# MrMIDI_L1.net
KiCad netlist of a schematic drawn in EAGLE
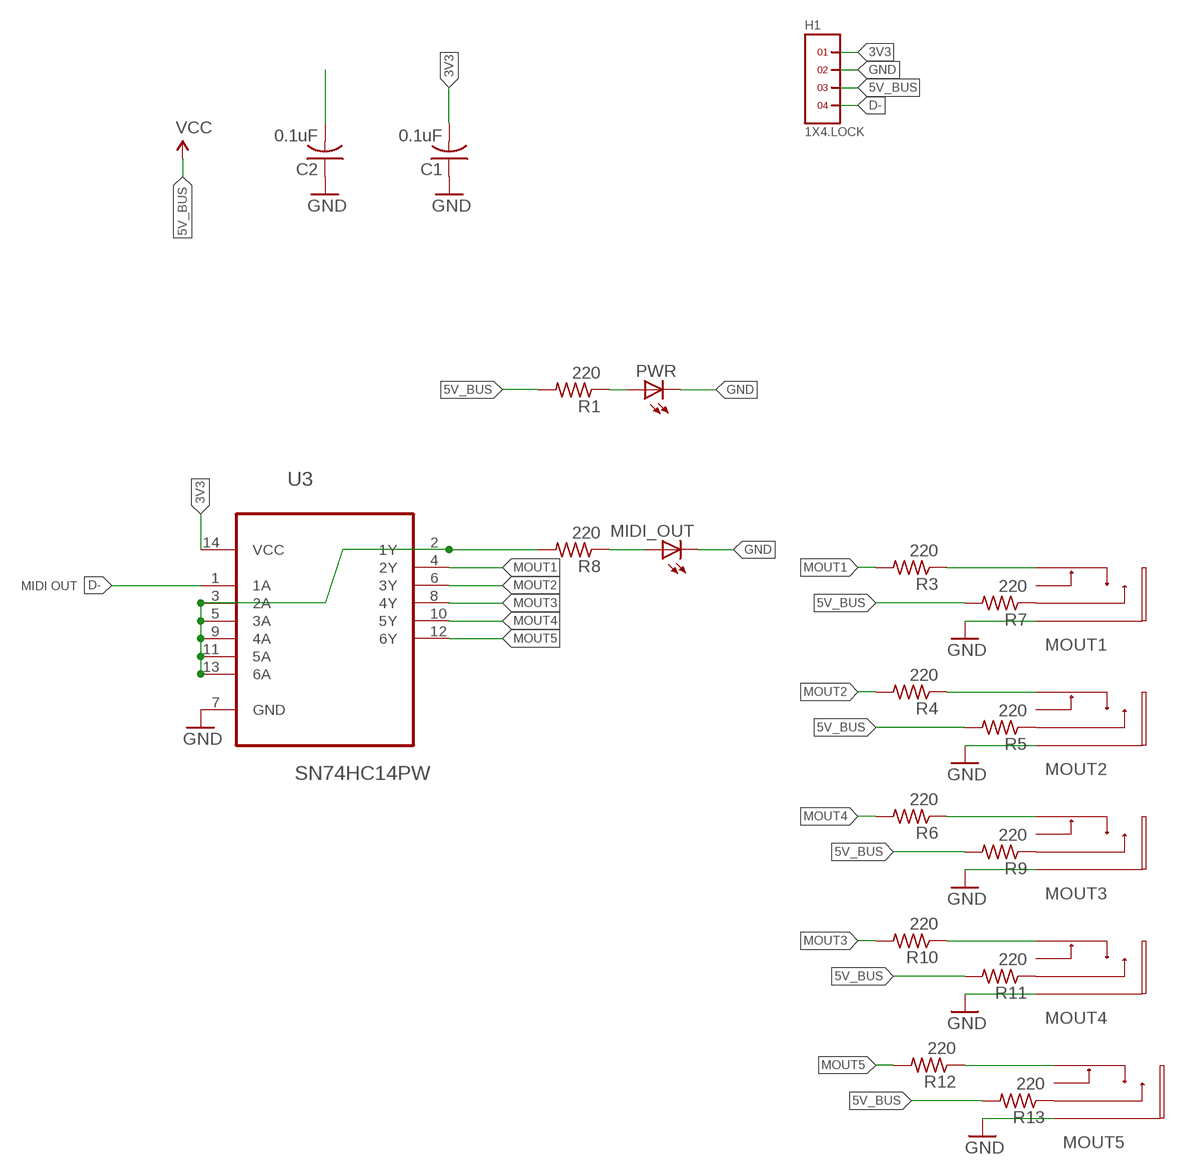
[diagram p0: schematic, sheet 1]

(export (version "E")
  (design (tool "Eeschema 10.0.6"))
  (components
    (comp (ref "C1")
      (value "0.1uF")
      (footprint "eagle-import:RCL_C0603K")
      (libsource (lib "eagle-import") (part "RCL_C-USC0603K"))
    )
    (comp (ref "C2")
      (value "0.1uF")
      (footprint "eagle-import:RCL_C0603K")
      (libsource (lib "eagle-import") (part "RCL_C-USC0603K"))
    )
    (comp (ref "H1")
      (value "1X4.LOCK")
      (footprint "eagle-import:1X4.LOCK")
      (libsource (lib "eagle-import") (part "1X4.LOCK"))
    )
    (comp (ref "MIDI_OUT")
      (value "LEDCHIPLED_0603")
      (footprint "eagle-import:CHIPLED_0603")
      (libsource (lib "eagle-import") (part "LEDCHIPLED_0603"))
    )
    (comp (ref "MOUT1")
      (value "PJ327E")
      (footprint "eagle-import:PJ327")
      (libsource (lib "eagle-import") (part "PJ327E"))
    )
    (comp (ref "MOUT2")
      (value "PJ327E")
      (footprint "eagle-import:PJ327")
      (libsource (lib "eagle-import") (part "PJ327E"))
    )
    (comp (ref "MOUT3")
      (value "PJ327E")
      (footprint "eagle-import:PJ327")
      (libsource (lib "eagle-import") (part "PJ327E"))
    )
    (comp (ref "MOUT4")
      (value "PJ327E")
      (footprint "eagle-import:PJ327")
      (libsource (lib "eagle-import") (part "PJ327E"))
    )
    (comp (ref "MOUT5")
      (value "PJ327E")
      (footprint "eagle-import:PJ327")
      (libsource (lib "eagle-import") (part "PJ327E"))
    )
    (comp (ref "PWR")
      (value "LEDCHIPLED_0603")
      (footprint "eagle-import:CHIPLED_0603")
      (libsource (lib "eagle-import") (part "LEDCHIPLED_0603"))
    )
    (comp (ref "R1")
      (value "220")
      (footprint "eagle-import:RCL_R0402")
      (libsource (lib "eagle-import") (part "RCL_R-US_R0402"))
    )
    (comp (ref "R3")
      (value "220")
      (footprint "eagle-import:RCL_R0402")
      (libsource (lib "eagle-import") (part "RCL_R-US_R0402"))
    )
    (comp (ref "R4")
      (value "220")
      (footprint "eagle-import:RCL_R0402")
      (libsource (lib "eagle-import") (part "RCL_R-US_R0402"))
    )
    (comp (ref "R5")
      (value "220")
      (footprint "eagle-import:RCL_R0402")
      (libsource (lib "eagle-import") (part "RCL_R-US_R0402"))
    )
    (comp (ref "R6")
      (value "220")
      (footprint "eagle-import:RCL_R0402")
      (libsource (lib "eagle-import") (part "RCL_R-US_R0402"))
    )
    (comp (ref "R7")
      (value "220")
      (footprint "eagle-import:RCL_R0402")
      (libsource (lib "eagle-import") (part "RCL_R-US_R0402"))
    )
    (comp (ref "R8")
      (value "220")
      (footprint "eagle-import:RCL_R0402")
      (libsource (lib "eagle-import") (part "RCL_R-US_R0402"))
    )
    (comp (ref "R9")
      (value "220")
      (footprint "eagle-import:RCL_R0402")
      (libsource (lib "eagle-import") (part "RCL_R-US_R0402"))
    )
    (comp (ref "R10")
      (value "220")
      (footprint "eagle-import:RCL_R0402")
      (libsource (lib "eagle-import") (part "RCL_R-US_R0402"))
    )
    (comp (ref "R11")
      (value "220")
      (footprint "eagle-import:RCL_R0402")
      (libsource (lib "eagle-import") (part "RCL_R-US_R0402"))
    )
    (comp (ref "R12")
      (value "220")
      (footprint "eagle-import:RCL_R0402")
      (libsource (lib "eagle-import") (part "RCL_R-US_R0402"))
    )
    (comp (ref "R13")
      (value "220")
      (footprint "eagle-import:RCL_R0402")
      (libsource (lib "eagle-import") (part "RCL_R-US_R0402"))
    )
    (comp (ref "U3")
      (value "SN74HC14PW")
      (footprint "eagle-import:SOP65P640X120-14N")
      (libsource (lib "eagle-import") (part "SN74HC14PW"))
    )
  )
  (nets
    (net (code "1") (name "3V3") (class "Default")
      (node (ref "C1") (pin "2") (pinfunction "2_2") (pintype "passive"))
      (node (ref "H1") (pin "1") (pinfunction "1_1") (pintype "bidirectional"))
      (node (ref "U3") (pin "14") (pinfunction "VCC_14") (pintype "power_in"))
    )
    (net (code "2") (name "5V_BUS") (class "Default")
      (node (ref "C2") (pin "2") (pinfunction "2_2") (pintype "passive"))
      (node (ref "H1") (pin "3") (pinfunction "3_3") (pintype "bidirectional"))
      (node (ref "R1") (pin "2") (pinfunction "2_2") (pintype "passive"))
      (node (ref "R11") (pin "2") (pinfunction "2_2") (pintype "passive"))
      (node (ref "R13") (pin "2") (pinfunction "2_2") (pintype "passive"))
      (node (ref "R5") (pin "2") (pinfunction "2_2") (pintype "passive"))
      (node (ref "R7") (pin "2") (pinfunction "2_2") (pintype "passive"))
      (node (ref "R9") (pin "2") (pinfunction "2_2") (pintype "passive"))
    )
    (net (code "3") (name "D-") (class "Default")
      (node (ref "H1") (pin "4") (pinfunction "4_4") (pintype "bidirectional"))
      (node (ref "U3") (pin "1") (pinfunction "1A_1") (pintype "input"))
    )
    (net (code "4") (name "GND") (class "Default")
      (node (ref "C1") (pin "1") (pinfunction "1_1") (pintype "passive"))
      (node (ref "C2") (pin "1") (pinfunction "1_1") (pintype "passive"))
      (node (ref "H1") (pin "2") (pinfunction "2_2") (pintype "bidirectional"))
      (node (ref "MIDI_OUT") (pin "C") (pinfunction "C_C") (pintype "passive"))
      (node (ref "MOUT1") (pin "P$1") (pinfunction "P$1_P$1") (pintype "bidirectional"))
      (node (ref "MOUT1") (pin "P$4") (pinfunction "P$1_P$4") (pintype "bidirectional"))
      (node (ref "MOUT2") (pin "P$1") (pinfunction "P$1_P$1") (pintype "bidirectional"))
      (node (ref "MOUT2") (pin "P$4") (pinfunction "P$1_P$4") (pintype "bidirectional"))
      (node (ref "MOUT3") (pin "P$1") (pinfunction "P$1_P$1") (pintype "bidirectional"))
      (node (ref "MOUT3") (pin "P$4") (pinfunction "P$1_P$4") (pintype "bidirectional"))
      (node (ref "MOUT4") (pin "P$1") (pinfunction "P$1_P$1") (pintype "bidirectional"))
      (node (ref "MOUT4") (pin "P$4") (pinfunction "P$1_P$4") (pintype "bidirectional"))
      (node (ref "MOUT5") (pin "P$1") (pinfunction "P$1_P$1") (pintype "bidirectional"))
      (node (ref "MOUT5") (pin "P$4") (pinfunction "P$1_P$4") (pintype "bidirectional"))
      (node (ref "PWR") (pin "C") (pinfunction "C_C") (pintype "passive"))
      (node (ref "U3") (pin "7") (pinfunction "GND_7") (pintype "passive"))
    )
    (net (code "5") (name "MOUT1") (class "Default")
      (node (ref "R3") (pin "2") (pinfunction "2_2") (pintype "passive"))
      (node (ref "U3") (pin "4") (pinfunction "2Y_4") (pintype "output"))
    )
    (net (code "6") (name "MOUT2") (class "Default")
      (node (ref "R4") (pin "2") (pinfunction "2_2") (pintype "passive"))
      (node (ref "U3") (pin "6") (pinfunction "3Y_6") (pintype "output"))
    )
    (net (code "7") (name "MOUT3") (class "Default")
      (node (ref "R10") (pin "2") (pinfunction "2_2") (pintype "passive"))
      (node (ref "U3") (pin "8") (pinfunction "4Y_8") (pintype "output"))
    )
    (net (code "8") (name "MOUT4") (class "Default")
      (node (ref "R6") (pin "2") (pinfunction "2_2") (pintype "passive"))
      (node (ref "U3") (pin "10") (pinfunction "5Y_10") (pintype "output"))
    )
    (net (code "9") (name "MOUT5") (class "Default")
      (node (ref "R12") (pin "2") (pinfunction "2_2") (pintype "passive"))
      (node (ref "U3") (pin "12") (pinfunction "6Y_12") (pintype "output"))
    )
    (net (code "10") (name "Net-(MIDI_OUT-PadA)") (class "Default")
      (node (ref "MIDI_OUT") (pin "A") (pinfunction "A_A") (pintype "passive"))
      (node (ref "R8") (pin "1") (pinfunction "1_1") (pintype "passive"))
    )
    (net (code "11") (name "Net-(MOUT1-PadP$2)") (class "Default")
      (node (ref "MOUT1") (pin "P$2") (pinfunction "P$2_P$2") (pintype "bidirectional"))
      (node (ref "R3") (pin "1") (pinfunction "1_1") (pintype "passive"))
    )
    (net (code "12") (name "Net-(MOUT1-PadP$3)") (class "Default")
      (node (ref "MOUT1") (pin "P$3") (pinfunction "P$3_P$3") (pintype "bidirectional"))
      (node (ref "R7") (pin "1") (pinfunction "1_1") (pintype "passive"))
    )
    (net (code "13") (name "Net-(MOUT2-PadP$2)") (class "Default")
      (node (ref "MOUT2") (pin "P$2") (pinfunction "P$2_P$2") (pintype "bidirectional"))
      (node (ref "R4") (pin "1") (pinfunction "1_1") (pintype "passive"))
    )
    (net (code "14") (name "Net-(MOUT2-PadP$3)") (class "Default")
      (node (ref "MOUT2") (pin "P$3") (pinfunction "P$3_P$3") (pintype "bidirectional"))
      (node (ref "R5") (pin "1") (pinfunction "1_1") (pintype "passive"))
    )
    (net (code "15") (name "Net-(MOUT3-PadP$2)") (class "Default")
      (node (ref "MOUT3") (pin "P$2") (pinfunction "P$2_P$2") (pintype "bidirectional"))
      (node (ref "R6") (pin "1") (pinfunction "1_1") (pintype "passive"))
    )
    (net (code "16") (name "Net-(MOUT3-PadP$3)") (class "Default")
      (node (ref "MOUT3") (pin "P$3") (pinfunction "P$3_P$3") (pintype "bidirectional"))
      (node (ref "R9") (pin "1") (pinfunction "1_1") (pintype "passive"))
    )
    (net (code "17") (name "Net-(MOUT4-PadP$2)") (class "Default")
      (node (ref "MOUT4") (pin "P$2") (pinfunction "P$2_P$2") (pintype "bidirectional"))
      (node (ref "R10") (pin "1") (pinfunction "1_1") (pintype "passive"))
    )
    (net (code "18") (name "Net-(MOUT4-PadP$3)") (class "Default")
      (node (ref "MOUT4") (pin "P$3") (pinfunction "P$3_P$3") (pintype "bidirectional"))
      (node (ref "R11") (pin "1") (pinfunction "1_1") (pintype "passive"))
    )
    (net (code "19") (name "Net-(MOUT5-PadP$2)") (class "Default")
      (node (ref "MOUT5") (pin "P$2") (pinfunction "P$2_P$2") (pintype "bidirectional"))
      (node (ref "R12") (pin "1") (pinfunction "1_1") (pintype "passive"))
    )
    (net (code "20") (name "Net-(MOUT5-PadP$3)") (class "Default")
      (node (ref "MOUT5") (pin "P$3") (pinfunction "P$3_P$3") (pintype "bidirectional"))
      (node (ref "R13") (pin "1") (pinfunction "1_1") (pintype "passive"))
    )
    (net (code "21") (name "Net-(PWR-PadA)") (class "Default")
      (node (ref "PWR") (pin "A") (pinfunction "A_A") (pintype "passive"))
      (node (ref "R1") (pin "1") (pinfunction "1_1") (pintype "passive"))
    )
    (net (code "22") (name "Net-(U3-1Y)") (class "Default")
      (node (ref "R8") (pin "2") (pinfunction "2_2") (pintype "passive"))
      (node (ref "U3") (pin "11") (pinfunction "5A_11") (pintype "input"))
      (node (ref "U3") (pin "13") (pinfunction "6A_13") (pintype "input"))
      (node (ref "U3") (pin "2") (pinfunction "1Y_2") (pintype "output"))
      (node (ref "U3") (pin "3") (pinfunction "2A_3") (pintype "input"))
      (node (ref "U3") (pin "5") (pinfunction "3A_5") (pintype "input"))
      (node (ref "U3") (pin "9") (pinfunction "4A_9") (pintype "input"))
    )
    (net (code "23") (name "unconnected-(MOUT1-PadP$5)") (class "Default")
      (node (ref "MOUT1") (pin "P$5") (pinfunction "P$5_P$5") (pintype "bidirectional"))
    )
    (net (code "24") (name "unconnected-(MOUT2-PadP$5)") (class "Default")
      (node (ref "MOUT2") (pin "P$5") (pinfunction "P$5_P$5") (pintype "bidirectional"))
    )
    (net (code "25") (name "unconnected-(MOUT3-PadP$5)") (class "Default")
      (node (ref "MOUT3") (pin "P$5") (pinfunction "P$5_P$5") (pintype "bidirectional"))
    )
    (net (code "26") (name "unconnected-(MOUT4-PadP$5)") (class "Default")
      (node (ref "MOUT4") (pin "P$5") (pinfunction "P$5_P$5") (pintype "bidirectional"))
    )
    (net (code "27") (name "unconnected-(MOUT5-PadP$5)") (class "Default")
      (node (ref "MOUT5") (pin "P$5") (pinfunction "P$5_P$5") (pintype "bidirectional"))
    )
  )
)
